# Layout.net
KiCad netlist of a schematic drawn in EAGLE
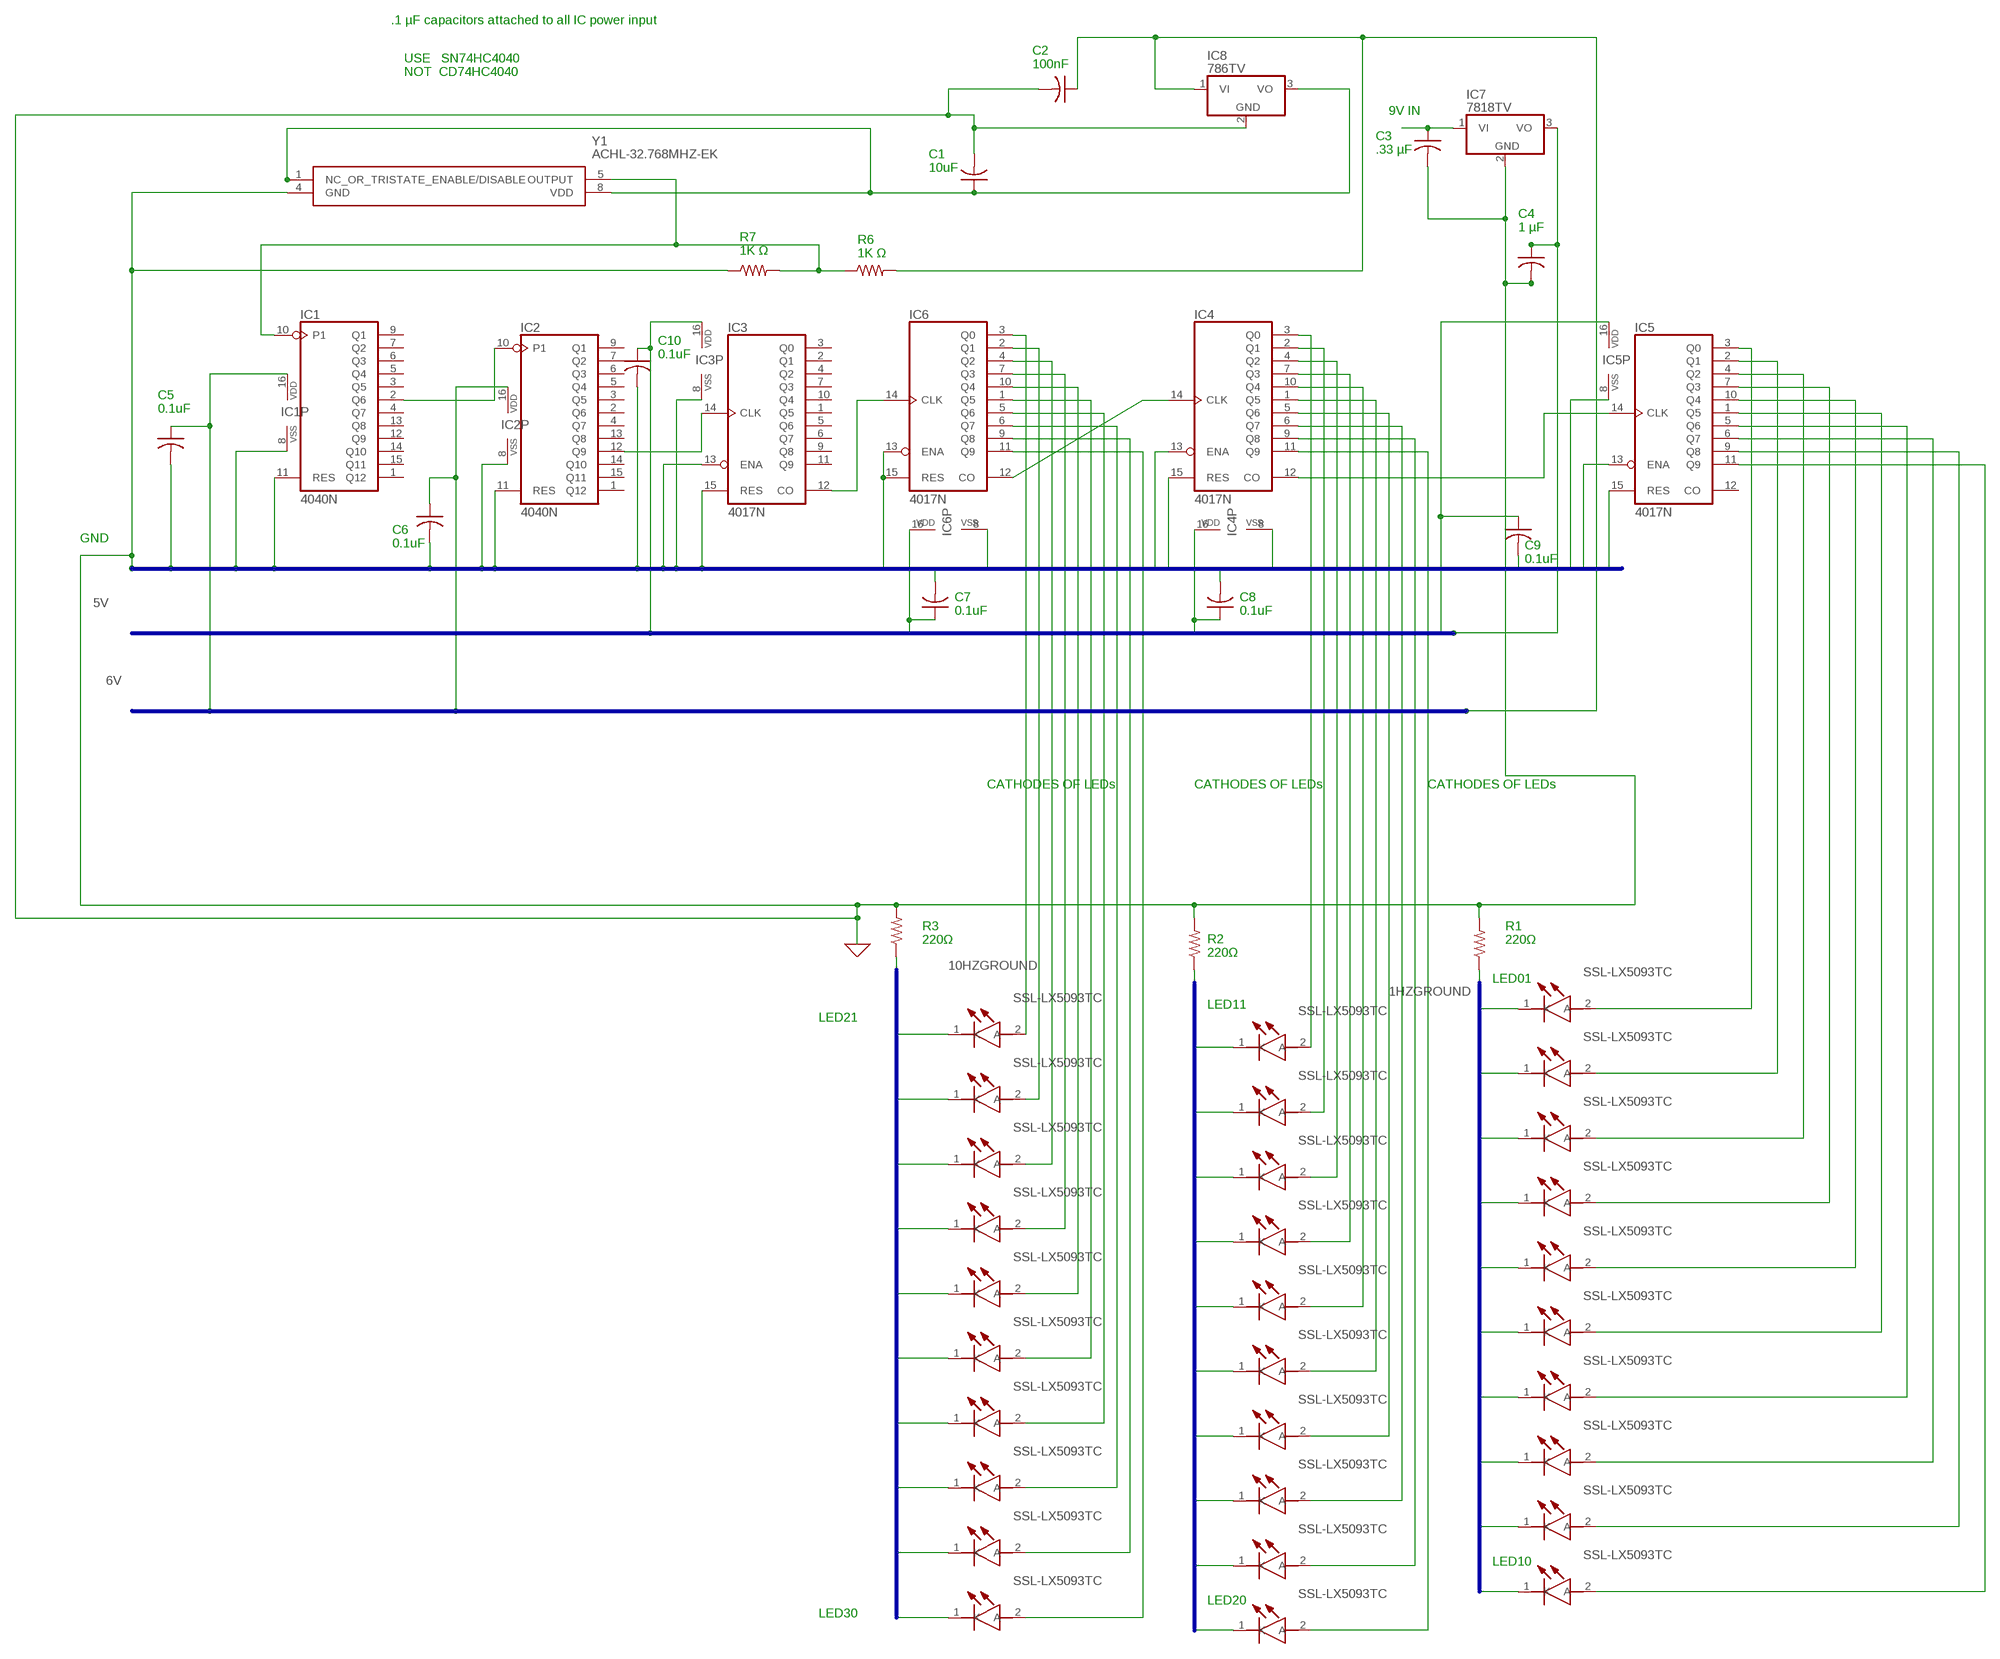
[diagram p0: schematic, sheet 1]

(export (version "E")
  (design (tool "Eeschema 10.0.6"))
  (components
    (comp (ref "C1")
      (value "1uF")
      (footprint "eagle-import:C075-063X106")
      (libsource (lib "eagle-import") (part "C-US075-063X106"))
    )
    (comp (ref "C2")
      (value ".33uF")
      (footprint "eagle-import:C075-063X106")
      (libsource (lib "eagle-import") (part "C-US075-063X106"))
    )
    (comp (ref "C3")
      (value "0.33uF")
      (footprint "eagle-import:C075-063X106")
      (libsource (lib "eagle-import") (part "C-US075-063X106"))
    )
    (comp (ref "C4")
      (value "1uF")
      (footprint "eagle-import:C075-063X106")
      (libsource (lib "eagle-import") (part "C-US075-063X106"))
    )
    (comp (ref "C5")
      (value ".1uF")
      (footprint "eagle-import:C075-063X106")
      (fields (field (name "SPICEPREFIX") "C"))
      (libsource (lib "eagle-import") (part "C-US075-063X106"))
    )
    (comp (ref "C6")
      (value ".1uF")
      (footprint "eagle-import:C075-063X106")
      (libsource (lib "eagle-import") (part "C-US075-063X106"))
    )
    (comp (ref "C7")
      (value ".1uF")
      (footprint "eagle-import:C075-063X106")
      (libsource (lib "eagle-import") (part "C-US075-063X106"))
    )
    (comp (ref "C8")
      (value ".1uF")
      (footprint "eagle-import:C075-063X106")
      (libsource (lib "eagle-import") (part "C-US075-063X106"))
    )
    (comp (ref "C9")
      (value ".1uF")
      (footprint "eagle-import:C075-063X106")
      (libsource (lib "eagle-import") (part "C-US075-063X106"))
    )
    (comp (ref "C10")
      (value ".1uF")
      (footprint "eagle-import:C075-063X106")
      (libsource (lib "eagle-import") (part "C-US075-063X106"))
    )
    (comp (ref "IC1")
      (value "4040N")
      (footprint "eagle-import:DIL16")
      (libsource (lib "eagle-import") (part "4040N"))
    )
    (comp (ref "IC2")
      (value "4040N")
      (footprint "eagle-import:DIL16")
      (libsource (lib "eagle-import") (part "4040N"))
    )
    (comp (ref "IC3")
      (value "4017N")
      (footprint "eagle-import:DIL16")
      (libsource (lib "eagle-import") (part "4017N"))
    )
    (comp (ref "IC4")
      (value "4017N")
      (footprint "eagle-import:DIL16")
      (libsource (lib "eagle-import") (part "4017N"))
    )
    (comp (ref "IC5")
      (value "4017N")
      (footprint "eagle-import:DIL16")
      (libsource (lib "eagle-import") (part "4017N"))
    )
    (comp (ref "IC6")
      (value "4017N")
      (footprint "eagle-import:DIL16")
      (libsource (lib "eagle-import") (part "4017N"))
    )
    (comp (ref "IC7")
      (value "7818TV")
      (footprint "eagle-import:TO220V")
      (fields (field (name "SPICEPREFIX") "J"))
      (libsource (lib "eagle-import") (part "78TV18"))
    )
    (comp (ref "IC8")
      (value "786TV")
      (footprint "eagle-import:TO220V")
      (libsource (lib "eagle-import") (part "78TV6"))
    )
    (comp (ref "LED1")
      (value "SSL-LX5093TC")
      (footprint "eagle-import:SSL-LX5093SGC_B")
      (fields (field (name "MOUSER_PART_NUMBER") "696-SSL-LX5093TC"))
      (libsource (lib "eagle-import") (part "SSL-LX5093TC"))
    )
    (comp (ref "LED2")
      (value "SSL-LX5093TC")
      (footprint "eagle-import:SSL-LX5093SGC_B")
      (fields (field (name "MOUSER_PART_NUMBER") "696-SSL-LX5093TC"))
      (libsource (lib "eagle-import") (part "SSL-LX5093TC"))
    )
    (comp (ref "LED3")
      (value "SSL-LX5093TC")
      (footprint "eagle-import:SSL-LX5093SGC_B")
      (fields (field (name "MOUSER_PART_NUMBER") "696-SSL-LX5093TC"))
      (libsource (lib "eagle-import") (part "SSL-LX5093TC"))
    )
    (comp (ref "LED4")
      (value "SSL-LX5093TC")
      (footprint "eagle-import:SSL-LX5093SGC_B")
      (fields (field (name "MOUSER_PART_NUMBER") "696-SSL-LX5093TC"))
      (libsource (lib "eagle-import") (part "SSL-LX5093TC"))
    )
    (comp (ref "LED5")
      (value "SSL-LX5093TC")
      (footprint "eagle-import:SSL-LX5093SGC_B")
      (fields (field (name "MOUSER_PART_NUMBER") "696-SSL-LX5093TC"))
      (libsource (lib "eagle-import") (part "SSL-LX5093TC"))
    )
    (comp (ref "LED6")
      (value "SSL-LX5093TC")
      (footprint "eagle-import:SSL-LX5093SGC_B")
      (fields (field (name "MOUSER_PART_NUMBER") "696-SSL-LX5093TC"))
      (libsource (lib "eagle-import") (part "SSL-LX5093TC"))
    )
    (comp (ref "LED7")
      (value "SSL-LX5093TC")
      (footprint "eagle-import:SSL-LX5093SGC_B")
      (fields (field (name "MOUSER_PART_NUMBER") "696-SSL-LX5093TC"))
      (libsource (lib "eagle-import") (part "SSL-LX5093TC"))
    )
    (comp (ref "LED8")
      (value "SSL-LX5093TC")
      (footprint "eagle-import:SSL-LX5093SGC_B")
      (fields (field (name "MOUSER_PART_NUMBER") "696-SSL-LX5093TC"))
      (libsource (lib "eagle-import") (part "SSL-LX5093TC"))
    )
    (comp (ref "LED9")
      (value "SSL-LX5093TC")
      (footprint "eagle-import:SSL-LX5093SGC_B")
      (fields (field (name "MOUSER_PART_NUMBER") "696-SSL-LX5093TC"))
      (libsource (lib "eagle-import") (part "SSL-LX5093TC"))
    )
    (comp (ref "LED10")
      (value "SSL-LX5093TC")
      (footprint "eagle-import:SSL-LX5093SGC_B")
      (fields (field (name "MOUSER_PART_NUMBER") "696-SSL-LX5093TC"))
      (libsource (lib "eagle-import") (part "SSL-LX5093TC"))
    )
    (comp (ref "LED11")
      (value "SSL-LX5093TC")
      (footprint "eagle-import:SSL-LX5093SGC_B")
      (fields (field (name "MOUSER_PART_NUMBER") "696-SSL-LX5093TC"))
      (libsource (lib "eagle-import") (part "SSL-LX5093TC"))
    )
    (comp (ref "LED12")
      (value "SSL-LX5093TC")
      (footprint "eagle-import:SSL-LX5093SGC_B")
      (fields (field (name "MOUSER_PART_NUMBER") "696-SSL-LX5093TC"))
      (libsource (lib "eagle-import") (part "SSL-LX5093TC"))
    )
    (comp (ref "LED13")
      (value "SSL-LX5093TC")
      (footprint "eagle-import:SSL-LX5093SGC_B")
      (fields (field (name "MOUSER_PART_NUMBER") "696-SSL-LX5093TC"))
      (libsource (lib "eagle-import") (part "SSL-LX5093TC"))
    )
    (comp (ref "LED14")
      (value "SSL-LX5093TC")
      (footprint "eagle-import:SSL-LX5093SGC_B")
      (fields (field (name "MOUSER_PART_NUMBER") "696-SSL-LX5093TC"))
      (libsource (lib "eagle-import") (part "SSL-LX5093TC"))
    )
    (comp (ref "LED15")
      (value "SSL-LX5093TC")
      (footprint "eagle-import:SSL-LX5093SGC_B")
      (fields (field (name "MOUSER_PART_NUMBER") "696-SSL-LX5093TC"))
      (libsource (lib "eagle-import") (part "SSL-LX5093TC"))
    )
    (comp (ref "LED16")
      (value "SSL-LX5093TC")
      (footprint "eagle-import:SSL-LX5093SGC_B")
      (fields (field (name "MOUSER_PART_NUMBER") "696-SSL-LX5093TC"))
      (libsource (lib "eagle-import") (part "SSL-LX5093TC"))
    )
    (comp (ref "LED17")
      (value "SSL-LX5093TC")
      (footprint "eagle-import:SSL-LX5093SGC_B")
      (fields (field (name "MOUSER_PART_NUMBER") "696-SSL-LX5093TC"))
      (libsource (lib "eagle-import") (part "SSL-LX5093TC"))
    )
    (comp (ref "LED18")
      (value "SSL-LX5093TC")
      (footprint "eagle-import:SSL-LX5093SGC_B")
      (fields (field (name "MOUSER_PART_NUMBER") "696-SSL-LX5093TC"))
      (libsource (lib "eagle-import") (part "SSL-LX5093TC"))
    )
    (comp (ref "LED19")
      (value "SSL-LX5093TC")
      (footprint "eagle-import:SSL-LX5093SGC_B")
      (fields (field (name "MOUSER_PART_NUMBER") "696-SSL-LX5093TC"))
      (libsource (lib "eagle-import") (part "SSL-LX5093TC"))
    )
    (comp (ref "LED20")
      (value "SSL-LX5093TC")
      (footprint "eagle-import:SSL-LX5093SGC_B")
      (fields (field (name "MOUSER_PART_NUMBER") "696-SSL-LX5093TC"))
      (libsource (lib "eagle-import") (part "SSL-LX5093TC"))
    )
    (comp (ref "LED21")
      (value "SSL-LX5093TC")
      (footprint "eagle-import:SSL-LX5093SGC_B")
      (fields (field (name "MOUSER_PART_NUMBER") "696-SSL-LX5093TC"))
      (libsource (lib "eagle-import") (part "SSL-LX5093TC"))
    )
    (comp (ref "LED22")
      (value "SSL-LX5093TC")
      (footprint "eagle-import:SSL-LX5093SGC_B")
      (fields (field (name "MOUSER_PART_NUMBER") "696-SSL-LX5093TC"))
      (libsource (lib "eagle-import") (part "SSL-LX5093TC"))
    )
    (comp (ref "LED23")
      (value "SSL-LX5093TC")
      (footprint "eagle-import:SSL-LX5093SGC_B")
      (fields (field (name "MOUSER_PART_NUMBER") "696-SSL-LX5093TC"))
      (libsource (lib "eagle-import") (part "SSL-LX5093TC"))
    )
    (comp (ref "LED24")
      (value "SSL-LX5093TC")
      (footprint "eagle-import:SSL-LX5093SGC_B")
      (fields (field (name "MOUSER_PART_NUMBER") "696-SSL-LX5093TC"))
      (libsource (lib "eagle-import") (part "SSL-LX5093TC"))
    )
    (comp (ref "LED25")
      (value "SSL-LX5093TC")
      (footprint "eagle-import:SSL-LX5093SGC_B")
      (fields (field (name "MOUSER_PART_NUMBER") "696-SSL-LX5093TC"))
      (libsource (lib "eagle-import") (part "SSL-LX5093TC"))
    )
    (comp (ref "LED26")
      (value "SSL-LX5093TC")
      (footprint "eagle-import:SSL-LX5093SGC_B")
      (fields (field (name "MOUSER_PART_NUMBER") "696-SSL-LX5093TC"))
      (libsource (lib "eagle-import") (part "SSL-LX5093TC"))
    )
    (comp (ref "LED27")
      (value "SSL-LX5093TC")
      (footprint "eagle-import:SSL-LX5093SGC_B")
      (fields (field (name "MOUSER_PART_NUMBER") "696-SSL-LX5093TC"))
      (libsource (lib "eagle-import") (part "SSL-LX5093TC"))
    )
    (comp (ref "LED28")
      (value "SSL-LX5093TC")
      (footprint "eagle-import:SSL-LX5093SGC_B")
      (fields (field (name "MOUSER_PART_NUMBER") "696-SSL-LX5093TC"))
      (libsource (lib "eagle-import") (part "SSL-LX5093TC"))
    )
    (comp (ref "LED29")
      (value "SSL-LX5093TC")
      (footprint "eagle-import:SSL-LX5093SGC_B")
      (fields (field (name "MOUSER_PART_NUMBER") "696-SSL-LX5093TC"))
      (libsource (lib "eagle-import") (part "SSL-LX5093TC"))
    )
    (comp (ref "LED30")
      (value "SSL-LX5093TC")
      (footprint "eagle-import:SSL-LX5093SGC_B")
      (fields (field (name "MOUSER_PART_NUMBER") "696-SSL-LX5093TC"))
      (libsource (lib "eagle-import") (part "SSL-LX5093TC"))
    )
    (comp (ref "R1")
      (value "220")
      (footprint "eagle-import:0207_12")
      (libsource (lib "eagle-import") (part "R-US_0207/12"))
    )
    (comp (ref "R2")
      (value "220")
      (footprint "eagle-import:0207_12")
      (libsource (lib "eagle-import") (part "R-US_0207/12"))
    )
    (comp (ref "R3")
      (value "220")
      (footprint "eagle-import:0207_12")
      (libsource (lib "eagle-import") (part "R-US_0207/12"))
    )
    (comp (ref "R6")
      (value "1k")
      (footprint "eagle-import:0309_12")
      (libsource (lib "eagle-import") (part "R-US_0309/12"))
    )
    (comp (ref "R7")
      (value "1k")
      (footprint "eagle-import:0309_12")
      (libsource (lib "eagle-import") (part "R-US_0309/12"))
    )
    (comp (ref "Y1")
      (value "ACHL-32.768MHZ-EK")
      (footprint "eagle-import:ACHL")
      (fields (field (name "MOUSER_PART_NUMBER") "815-ACHL-32.768-EK"))
      (libsource (lib "eagle-import") (part "ACHL-32.768MHZ-EK"))
    )
  )
  (nets
    (net (code "1") (name "/1HZGROUND") (class "Default")
      (node (ref "LED1") (pin "1") (pinfunction "K_1") (pintype "bidirectional"))
      (node (ref "LED10") (pin "1") (pinfunction "K_1") (pintype "bidirectional"))
      (node (ref "LED2") (pin "1") (pinfunction "K_1") (pintype "bidirectional"))
      (node (ref "LED3") (pin "1") (pinfunction "K_1") (pintype "bidirectional"))
      (node (ref "LED4") (pin "1") (pinfunction "K_1") (pintype "bidirectional"))
      (node (ref "LED5") (pin "1") (pinfunction "K_1") (pintype "bidirectional"))
      (node (ref "LED6") (pin "1") (pinfunction "K_1") (pintype "bidirectional"))
      (node (ref "LED7") (pin "1") (pinfunction "K_1") (pintype "bidirectional"))
      (node (ref "LED8") (pin "1") (pinfunction "K_1") (pintype "bidirectional"))
      (node (ref "LED9") (pin "1") (pinfunction "K_1") (pintype "bidirectional"))
      (node (ref "R1") (pin "1") (pinfunction "1_1") (pintype "passive"))
    )
    (net (code "2") (name "/5V") (class "Default")
      (node (ref "C10") (pin "1") (pinfunction "1_1") (pintype "passive"))
      (node (ref "C4") (pin "1") (pinfunction "1_1") (pintype "passive"))
      (node (ref "C7") (pin "1") (pinfunction "1_1") (pintype "passive"))
      (node (ref "C8") (pin "1") (pinfunction "1_1") (pintype "passive"))
      (node (ref "C9") (pin "1") (pinfunction "1_1") (pintype "passive"))
      (node (ref "IC3") (pin "16") (pinfunction "VDD_16") (pintype "power_in"))
      (node (ref "IC4") (pin "16") (pinfunction "VDD_16") (pintype "power_in"))
      (node (ref "IC5") (pin "16") (pinfunction "VDD_16") (pintype "power_in"))
      (node (ref "IC6") (pin "16") (pinfunction "VDD_16") (pintype "power_in"))
      (node (ref "IC7") (pin "3") (pinfunction "VO_3") (pintype "passive"))
    )
    (net (code "3") (name "/6V") (class "Default")
      (node (ref "C2") (pin "1") (pinfunction "1_1") (pintype "passive"))
      (node (ref "C5") (pin "1") (pinfunction "1_1") (pintype "passive"))
      (node (ref "C6") (pin "1") (pinfunction "1_1") (pintype "passive"))
      (node (ref "IC1") (pin "16") (pinfunction "VDD_16") (pintype "power_in"))
      (node (ref "IC2") (pin "16") (pinfunction "VDD_16") (pintype "power_in"))
      (node (ref "IC8") (pin "1") (pinfunction "VI_1") (pintype "input"))
      (node (ref "R6") (pin "2") (pinfunction "2_2") (pintype "passive"))
    )
    (net (code "4") (name "/10HZGROUND") (class "Default")
      (node (ref "LED11") (pin "1") (pinfunction "K_1") (pintype "bidirectional"))
      (node (ref "LED12") (pin "1") (pinfunction "K_1") (pintype "bidirectional"))
      (node (ref "LED13") (pin "1") (pinfunction "K_1") (pintype "bidirectional"))
      (node (ref "LED14") (pin "1") (pinfunction "K_1") (pintype "bidirectional"))
      (node (ref "LED15") (pin "1") (pinfunction "K_1") (pintype "bidirectional"))
      (node (ref "LED16") (pin "1") (pinfunction "K_1") (pintype "bidirectional"))
      (node (ref "LED17") (pin "1") (pinfunction "K_1") (pintype "bidirectional"))
      (node (ref "LED18") (pin "1") (pinfunction "K_1") (pintype "bidirectional"))
      (node (ref "LED19") (pin "1") (pinfunction "K_1") (pintype "bidirectional"))
      (node (ref "LED20") (pin "1") (pinfunction "K_1") (pintype "bidirectional"))
      (node (ref "R2") (pin "1") (pinfunction "1_1") (pintype "passive"))
    )
    (net (code "5") (name "/100HZGROUND") (class "Default")
      (node (ref "LED21") (pin "1") (pinfunction "K_1") (pintype "bidirectional"))
      (node (ref "LED22") (pin "1") (pinfunction "K_1") (pintype "bidirectional"))
      (node (ref "LED23") (pin "1") (pinfunction "K_1") (pintype "bidirectional"))
      (node (ref "LED24") (pin "1") (pinfunction "K_1") (pintype "bidirectional"))
      (node (ref "LED25") (pin "1") (pinfunction "K_1") (pintype "bidirectional"))
      (node (ref "LED26") (pin "1") (pinfunction "K_1") (pintype "bidirectional"))
      (node (ref "LED27") (pin "1") (pinfunction "K_1") (pintype "bidirectional"))
      (node (ref "LED28") (pin "1") (pinfunction "K_1") (pintype "bidirectional"))
      (node (ref "LED29") (pin "1") (pinfunction "K_1") (pintype "bidirectional"))
      (node (ref "LED30") (pin "1") (pinfunction "K_1") (pintype "bidirectional"))
      (node (ref "R3") (pin "1") (pinfunction "1_1") (pintype "passive"))
    )
    (net (code "10") (name "GND") (class "Default")
      (node (ref "C1") (pin "2") (pinfunction "2_2") (pintype "passive"))
      (node (ref "C10") (pin "2") (pinfunction "2_2") (pintype "passive"))
      (node (ref "C2") (pin "2") (pinfunction "2_2") (pintype "passive"))
      (node (ref "C3") (pin "2") (pinfunction "2_2") (pintype "passive"))
      (node (ref "C4") (pin "2") (pinfunction "2_2") (pintype "passive"))
      (node (ref "C5") (pin "2") (pinfunction "2_2") (pintype "passive"))
      (node (ref "C6") (pin "2") (pinfunction "2_2") (pintype "passive"))
      (node (ref "C7") (pin "2") (pinfunction "2_2") (pintype "passive"))
      (node (ref "C8") (pin "2") (pinfunction "2_2") (pintype "passive"))
      (node (ref "C9") (pin "2") (pinfunction "2_2") (pintype "passive"))
      (node (ref "IC1") (pin "11") (pinfunction "RES_11") (pintype "input"))
      (node (ref "IC1") (pin "8") (pinfunction "VSS_8") (pintype "power_in"))
      (node (ref "IC2") (pin "11") (pinfunction "RES_11") (pintype "input"))
      (node (ref "IC2") (pin "8") (pinfunction "VSS_8") (pintype "power_in"))
      (node (ref "IC3") (pin "13") (pinfunction "ENA_13") (pintype "input"))
      (node (ref "IC3") (pin "15") (pinfunction "RES_15") (pintype "input"))
      (node (ref "IC3") (pin "8") (pinfunction "VSS_8") (pintype "power_in"))
      (node (ref "IC4") (pin "13") (pinfunction "ENA_13") (pintype "input"))
      (node (ref "IC4") (pin "15") (pinfunction "RES_15") (pintype "input"))
      (node (ref "IC4") (pin "8") (pinfunction "VSS_8") (pintype "power_in"))
      (node (ref "IC5") (pin "13") (pinfunction "ENA_13") (pintype "input"))
      (node (ref "IC5") (pin "15") (pinfunction "RES_15") (pintype "input"))
      (node (ref "IC5") (pin "8") (pinfunction "VSS_8") (pintype "power_in"))
      (node (ref "IC6") (pin "13") (pinfunction "ENA_13") (pintype "input"))
      (node (ref "IC6") (pin "15") (pinfunction "RES_15") (pintype "input"))
      (node (ref "IC6") (pin "8") (pinfunction "VSS_8") (pintype "power_in"))
      (node (ref "IC7") (pin "2") (pinfunction "GND_2") (pintype "passive"))
      (node (ref "IC8") (pin "2") (pinfunction "GND_2") (pintype "passive"))
      (node (ref "R1") (pin "2") (pinfunction "2_2") (pintype "passive"))
      (node (ref "R2") (pin "2") (pinfunction "2_2") (pintype "passive"))
      (node (ref "R3") (pin "2") (pinfunction "2_2") (pintype "passive"))
      (node (ref "R7") (pin "1") (pinfunction "1_1") (pintype "passive"))
      (node (ref "Y1") (pin "4") (pinfunction "GND_4") (pintype "bidirectional"))
    )
    (net (code "11") (name "Net-(IC1A-P1)") (class "Default")
      (node (ref "IC1") (pin "10") (pinfunction "P1_10") (pintype "input"))
      (node (ref "R6") (pin "1") (pinfunction "1_1") (pintype "passive"))
      (node (ref "R7") (pin "2") (pinfunction "2_2") (pintype "passive"))
      (node (ref "Y1") (pin "5") (pinfunction "OUTPUT_5") (pintype "bidirectional"))
    )
    (net (code "12") (name "Net-(IC1A-Q6)") (class "Default")
      (node (ref "IC1") (pin "2") (pinfunction "Q6_2") (pintype "output"))
      (node (ref "IC2") (pin "10") (pinfunction "P1_10") (pintype "input"))
    )
    (net (code "13") (name "Net-(IC2A-Q9)") (class "Default")
      (node (ref "IC2") (pin "12") (pinfunction "Q9_12") (pintype "output"))
      (node (ref "IC3") (pin "14") (pinfunction "CLK_14") (pintype "input"))
    )
    (net (code "14") (name "Net-(IC3A-CO)") (class "Default")
      (node (ref "IC3") (pin "12") (pinfunction "CO_12") (pintype "output"))
      (node (ref "IC6") (pin "14") (pinfunction "CLK_14") (pintype "input"))
    )
    (net (code "15") (name "Net-(IC4A-CLK)") (class "Default")
      (node (ref "IC4") (pin "14") (pinfunction "CLK_14") (pintype "input"))
      (node (ref "IC6") (pin "12") (pinfunction "CO_12") (pintype "output"))
    )
    (net (code "16") (name "Net-(IC4A-CO)") (class "Default")
      (node (ref "IC4") (pin "12") (pinfunction "CO_12") (pintype "output"))
      (node (ref "IC5") (pin "14") (pinfunction "CLK_14") (pintype "input"))
    )
    (net (code "17") (name "Net-(IC4A-Q0)") (class "Default")
      (node (ref "IC4") (pin "3") (pinfunction "Q0_3") (pintype "output"))
      (node (ref "LED11") (pin "2") (pinfunction "A_2") (pintype "bidirectional"))
    )
    (net (code "18") (name "Net-(IC4A-Q1)") (class "Default")
      (node (ref "IC4") (pin "2") (pinfunction "Q1_2") (pintype "output"))
      (node (ref "LED12") (pin "2") (pinfunction "A_2") (pintype "bidirectional"))
    )
    (net (code "19") (name "Net-(IC4A-Q2)") (class "Default")
      (node (ref "IC4") (pin "4") (pinfunction "Q2_4") (pintype "output"))
      (node (ref "LED13") (pin "2") (pinfunction "A_2") (pintype "bidirectional"))
    )
    (net (code "20") (name "Net-(IC4A-Q3)") (class "Default")
      (node (ref "IC4") (pin "7") (pinfunction "Q3_7") (pintype "output"))
      (node (ref "LED14") (pin "2") (pinfunction "A_2") (pintype "bidirectional"))
    )
    (net (code "21") (name "Net-(IC4A-Q4)") (class "Default")
      (node (ref "IC4") (pin "10") (pinfunction "Q4_10") (pintype "output"))
      (node (ref "LED15") (pin "2") (pinfunction "A_2") (pintype "bidirectional"))
    )
    (net (code "22") (name "Net-(IC4A-Q5)") (class "Default")
      (node (ref "IC4") (pin "1") (pinfunction "Q5_1") (pintype "output"))
      (node (ref "LED16") (pin "2") (pinfunction "A_2") (pintype "bidirectional"))
    )
    (net (code "23") (name "Net-(IC4A-Q6)") (class "Default")
      (node (ref "IC4") (pin "5") (pinfunction "Q6_5") (pintype "output"))
      (node (ref "LED17") (pin "2") (pinfunction "A_2") (pintype "bidirectional"))
    )
    (net (code "24") (name "Net-(IC4A-Q7)") (class "Default")
      (node (ref "IC4") (pin "6") (pinfunction "Q7_6") (pintype "output"))
      (node (ref "LED18") (pin "2") (pinfunction "A_2") (pintype "bidirectional"))
    )
    (net (code "25") (name "Net-(IC4A-Q8)") (class "Default")
      (node (ref "IC4") (pin "9") (pinfunction "Q8_9") (pintype "output"))
      (node (ref "LED19") (pin "2") (pinfunction "A_2") (pintype "bidirectional"))
    )
    (net (code "26") (name "Net-(IC4A-Q9)") (class "Default")
      (node (ref "IC4") (pin "11") (pinfunction "Q9_11") (pintype "output"))
      (node (ref "LED20") (pin "2") (pinfunction "A_2") (pintype "bidirectional"))
    )
    (net (code "27") (name "Net-(IC5A-Q0)") (class "Default")
      (node (ref "IC5") (pin "3") (pinfunction "Q0_3") (pintype "output"))
      (node (ref "LED1") (pin "2") (pinfunction "A_2") (pintype "bidirectional"))
    )
    (net (code "28") (name "Net-(IC5A-Q1)") (class "Default")
      (node (ref "IC5") (pin "2") (pinfunction "Q1_2") (pintype "output"))
      (node (ref "LED2") (pin "2") (pinfunction "A_2") (pintype "bidirectional"))
    )
    (net (code "29") (name "Net-(IC5A-Q2)") (class "Default")
      (node (ref "IC5") (pin "4") (pinfunction "Q2_4") (pintype "output"))
      (node (ref "LED3") (pin "2") (pinfunction "A_2") (pintype "bidirectional"))
    )
    (net (code "30") (name "Net-(IC5A-Q3)") (class "Default")
      (node (ref "IC5") (pin "7") (pinfunction "Q3_7") (pintype "output"))
      (node (ref "LED4") (pin "2") (pinfunction "A_2") (pintype "bidirectional"))
    )
    (net (code "31") (name "Net-(IC5A-Q4)") (class "Default")
      (node (ref "IC5") (pin "10") (pinfunction "Q4_10") (pintype "output"))
      (node (ref "LED5") (pin "2") (pinfunction "A_2") (pintype "bidirectional"))
    )
    (net (code "32") (name "Net-(IC5A-Q5)") (class "Default")
      (node (ref "IC5") (pin "1") (pinfunction "Q5_1") (pintype "output"))
      (node (ref "LED6") (pin "2") (pinfunction "A_2") (pintype "bidirectional"))
    )
    (net (code "33") (name "Net-(IC5A-Q6)") (class "Default")
      (node (ref "IC5") (pin "5") (pinfunction "Q6_5") (pintype "output"))
      (node (ref "LED7") (pin "2") (pinfunction "A_2") (pintype "bidirectional"))
    )
    (net (code "34") (name "Net-(IC5A-Q7)") (class "Default")
      (node (ref "IC5") (pin "6") (pinfunction "Q7_6") (pintype "output"))
      (node (ref "LED8") (pin "2") (pinfunction "A_2") (pintype "bidirectional"))
    )
    (net (code "35") (name "Net-(IC5A-Q8)") (class "Default")
      (node (ref "IC5") (pin "9") (pinfunction "Q8_9") (pintype "output"))
      (node (ref "LED9") (pin "2") (pinfunction "A_2") (pintype "bidirectional"))
    )
    (net (code "36") (name "Net-(IC5A-Q9)") (class "Default")
      (node (ref "IC5") (pin "11") (pinfunction "Q9_11") (pintype "output"))
      (node (ref "LED10") (pin "2") (pinfunction "A_2") (pintype "bidirectional"))
    )
    (net (code "37") (name "Net-(IC6A-Q0)") (class "Default")
      (node (ref "IC6") (pin "3") (pinfunction "Q0_3") (pintype "output"))
      (node (ref "LED21") (pin "2") (pinfunction "A_2") (pintype "bidirectional"))
    )
    (net (code "38") (name "Net-(IC6A-Q1)") (class "Default")
      (node (ref "IC6") (pin "2") (pinfunction "Q1_2") (pintype "output"))
      (node (ref "LED22") (pin "2") (pinfunction "A_2") (pintype "bidirectional"))
    )
    (net (code "39") (name "Net-(IC6A-Q2)") (class "Default")
      (node (ref "IC6") (pin "4") (pinfunction "Q2_4") (pintype "output"))
      (node (ref "LED23") (pin "2") (pinfunction "A_2") (pintype "bidirectional"))
    )
    (net (code "40") (name "Net-(IC6A-Q3)") (class "Default")
      (node (ref "IC6") (pin "7") (pinfunction "Q3_7") (pintype "output"))
      (node (ref "LED24") (pin "2") (pinfunction "A_2") (pintype "bidirectional"))
    )
    (net (code "41") (name "Net-(IC6A-Q4)") (class "Default")
      (node (ref "IC6") (pin "10") (pinfunction "Q4_10") (pintype "output"))
      (node (ref "LED25") (pin "2") (pinfunction "A_2") (pintype "bidirectional"))
    )
    (net (code "42") (name "Net-(IC6A-Q5)") (class "Default")
      (node (ref "IC6") (pin "1") (pinfunction "Q5_1") (pintype "output"))
      (node (ref "LED26") (pin "2") (pinfunction "A_2") (pintype "bidirectional"))
    )
    (net (code "43") (name "Net-(IC6A-Q6)") (class "Default")
      (node (ref "IC6") (pin "5") (pinfunction "Q6_5") (pintype "output"))
      (node (ref "LED27") (pin "2") (pinfunction "A_2") (pintype "bidirectional"))
    )
    (net (code "44") (name "Net-(IC6A-Q7)") (class "Default")
      (node (ref "IC6") (pin "6") (pinfunction "Q7_6") (pintype "output"))
      (node (ref "LED28") (pin "2") (pinfunction "A_2") (pintype "bidirectional"))
    )
    (net (code "45") (name "Net-(IC6A-Q8)") (class "Default")
      (node (ref "IC6") (pin "9") (pinfunction "Q8_9") (pintype "output"))
      (node (ref "LED29") (pin "2") (pinfunction "A_2") (pintype "bidirectional"))
    )
    (net (code "46") (name "Net-(IC6A-Q9)") (class "Default")
      (node (ref "IC6") (pin "11") (pinfunction "Q9_11") (pintype "output"))
      (node (ref "LED30") (pin "2") (pinfunction "A_2") (pintype "bidirectional"))
    )
    (net (code "47") (name "Net-(IC7-VI)") (class "Default")
      (node (ref "C3") (pin "1") (pinfunction "1_1") (pintype "passive"))
      (node (ref "IC7") (pin "1") (pinfunction "VI_1") (pintype "input"))
    )
    (net (code "48") (name "Net-(IC8-VO)") (class "Default")
      (node (ref "C1") (pin "1") (pinfunction "1_1") (pintype "passive"))
      (node (ref "IC8") (pin "3") (pinfunction "VO_3") (pintype "passive"))
      (node (ref "Y1") (pin "1") (pinfunction "NC_OR_TRISTATE_ENABLE/DISABLE_1") (pintype "bidirectional"))
      (node (ref "Y1") (pin "8") (pinfunction "VDD_8") (pintype "bidirectional"))
    )
    (net (code "49") (name "unconnected-(IC1A-Q1-Pad9)") (class "Default")
      (node (ref "IC1") (pin "9") (pinfunction "Q1_9") (pintype "output"))
    )
    (net (code "50") (name "unconnected-(IC1A-Q2-Pad7)") (class "Default")
      (node (ref "IC1") (pin "7") (pinfunction "Q2_7") (pintype "output"))
    )
    (net (code "51") (name "unconnected-(IC1A-Q3-Pad6)") (class "Default")
      (node (ref "IC1") (pin "6") (pinfunction "Q3_6") (pintype "output"))
    )
    (net (code "52") (name "unconnected-(IC1A-Q4-Pad5)") (class "Default")
      (node (ref "IC1") (pin "5") (pinfunction "Q4_5") (pintype "output"))
    )
    (net (code "53") (name "unconnected-(IC1A-Q5-Pad3)") (class "Default")
      (node (ref "IC1") (pin "3") (pinfunction "Q5_3") (pintype "output"))
    )
    (net (code "54") (name "unconnected-(IC1A-Q7-Pad4)") (class "Default")
      (node (ref "IC1") (pin "4") (pinfunction "Q7_4") (pintype "output"))
    )
    (net (code "55") (name "unconnected-(IC1A-Q8-Pad13)") (class "Default")
      (node (ref "IC1") (pin "13") (pinfunction "Q8_13") (pintype "output"))
    )
    (net (code "56") (name "unconnected-(IC1A-Q9-Pad12)") (class "Default")
      (node (ref "IC1") (pin "12") (pinfunction "Q9_12") (pintype "output"))
    )
    (net (code "57") (name "unconnected-(IC1A-Q10-Pad14)") (class "Default")
      (node (ref "IC1") (pin "14") (pinfunction "Q10_14") (pintype "output"))
    )
    (net (code "58") (name "unconnected-(IC1A-Q11-Pad15)") (class "Default")
      (node (ref "IC1") (pin "15") (pinfunction "Q11_15") (pintype "output"))
    )
    (net (code "59") (name "unconnected-(IC1A-Q12-Pad1)") (class "Default")
      (node (ref "IC1") (pin "1") (pinfunction "Q12_1") (pintype "output"))
    )
    (net (code "60") (name "unconnected-(IC2A-Q1-Pad9)") (class "Default")
      (node (ref "IC2") (pin "9") (pinfunction "Q1_9") (pintype "output"))
    )
    (net (code "61") (name "unconnected-(IC2A-Q2-Pad7)") (class "Default")
      (node (ref "IC2") (pin "7") (pinfunction "Q2_7") (pintype "output"))
    )
    (net (code "62") (name "unconnected-(IC2A-Q3-Pad6)") (class "Default")
      (node (ref "IC2") (pin "6") (pinfunction "Q3_6") (pintype "output"))
    )
    (net (code "63") (name "unconnected-(IC2A-Q4-Pad5)") (class "Default")
      (node (ref "IC2") (pin "5") (pinfunction "Q4_5") (pintype "output"))
    )
    (net (code "64") (name "unconnected-(IC2A-Q5-Pad3)") (class "Default")
      (node (ref "IC2") (pin "3") (pinfunction "Q5_3") (pintype "output"))
    )
    (net (code "65") (name "unconnected-(IC2A-Q6-Pad2)") (class "Default")
      (node (ref "IC2") (pin "2") (pinfunction "Q6_2") (pintype "output"))
    )
    (net (code "66") (name "unconnected-(IC2A-Q7-Pad4)") (class "Default")
      (node (ref "IC2") (pin "4") (pinfunction "Q7_4") (pintype "output"))
    )
    (net (code "67") (name "unconnected-(IC2A-Q8-Pad13)") (class "Default")
      (node (ref "IC2") (pin "13") (pinfunction "Q8_13") (pintype "output"))
    )
    (net (code "68") (name "unconnected-(IC2A-Q10-Pad14)") (class "Default")
      (node (ref "IC2") (pin "14") (pinfunction "Q10_14") (pintype "output"))
    )
    (net (code "69") (name "unconnected-(IC2A-Q11-Pad15)") (class "Default")
      (node (ref "IC2") (pin "15") (pinfunction "Q11_15") (pintype "output"))
    )
    (net (code "70") (name "unconnected-(IC2A-Q12-Pad1)") (class "Default")
      (node (ref "IC2") (pin "1") (pinfunction "Q12_1") (pintype "output"))
    )
    (net (code "71") (name "unconnected-(IC3A-Q0-Pad3)") (class "Default")
      (node (ref "IC3") (pin "3") (pinfunction "Q0_3") (pintype "output"))
    )
    (net (code "72") (name "unconnected-(IC3A-Q1-Pad2)") (class "Default")
      (node (ref "IC3") (pin "2") (pinfunction "Q1_2") (pintype "output"))
    )
    (net (code "73") (name "unconnected-(IC3A-Q2-Pad4)") (class "Default")
      (node (ref "IC3") (pin "4") (pinfunction "Q2_4") (pintype "output"))
    )
    (net (code "74") (name "unconnected-(IC3A-Q3-Pad7)") (class "Default")
      (node (ref "IC3") (pin "7") (pinfunction "Q3_7") (pintype "output"))
    )
    (net (code "75") (name "unconnected-(IC3A-Q4-Pad10)") (class "Default")
      (node (ref "IC3") (pin "10") (pinfunction "Q4_10") (pintype "output"))
    )
    (net (code "76") (name "unconnected-(IC3A-Q5-Pad1)") (class "Default")
      (node (ref "IC3") (pin "1") (pinfunction "Q5_1") (pintype "output"))
    )
    (net (code "77") (name "unconnected-(IC3A-Q6-Pad5)") (class "Default")
      (node (ref "IC3") (pin "5") (pinfunction "Q6_5") (pintype "output"))
    )
    (net (code "78") (name "unconnected-(IC3A-Q7-Pad6)") (class "Default")
      (node (ref "IC3") (pin "6") (pinfunction "Q7_6") (pintype "output"))
    )
    (net (code "79") (name "unconnected-(IC3A-Q8-Pad9)") (class "Default")
      (node (ref "IC3") (pin "9") (pinfunction "Q8_9") (pintype "output"))
    )
    (net (code "80") (name "unconnected-(IC3A-Q9-Pad11)") (class "Default")
      (node (ref "IC3") (pin "11") (pinfunction "Q9_11") (pintype "output"))
    )
    (net (code "81") (name "unconnected-(IC5A-CO-Pad12)") (class "Default")
      (node (ref "IC5") (pin "12") (pinfunction "CO_12") (pintype "output"))
    )
  )
)
